# SCH_Bob_Endstops_2022-07-10.net
KiCad netlist of a schematic drawn in EasyEDA
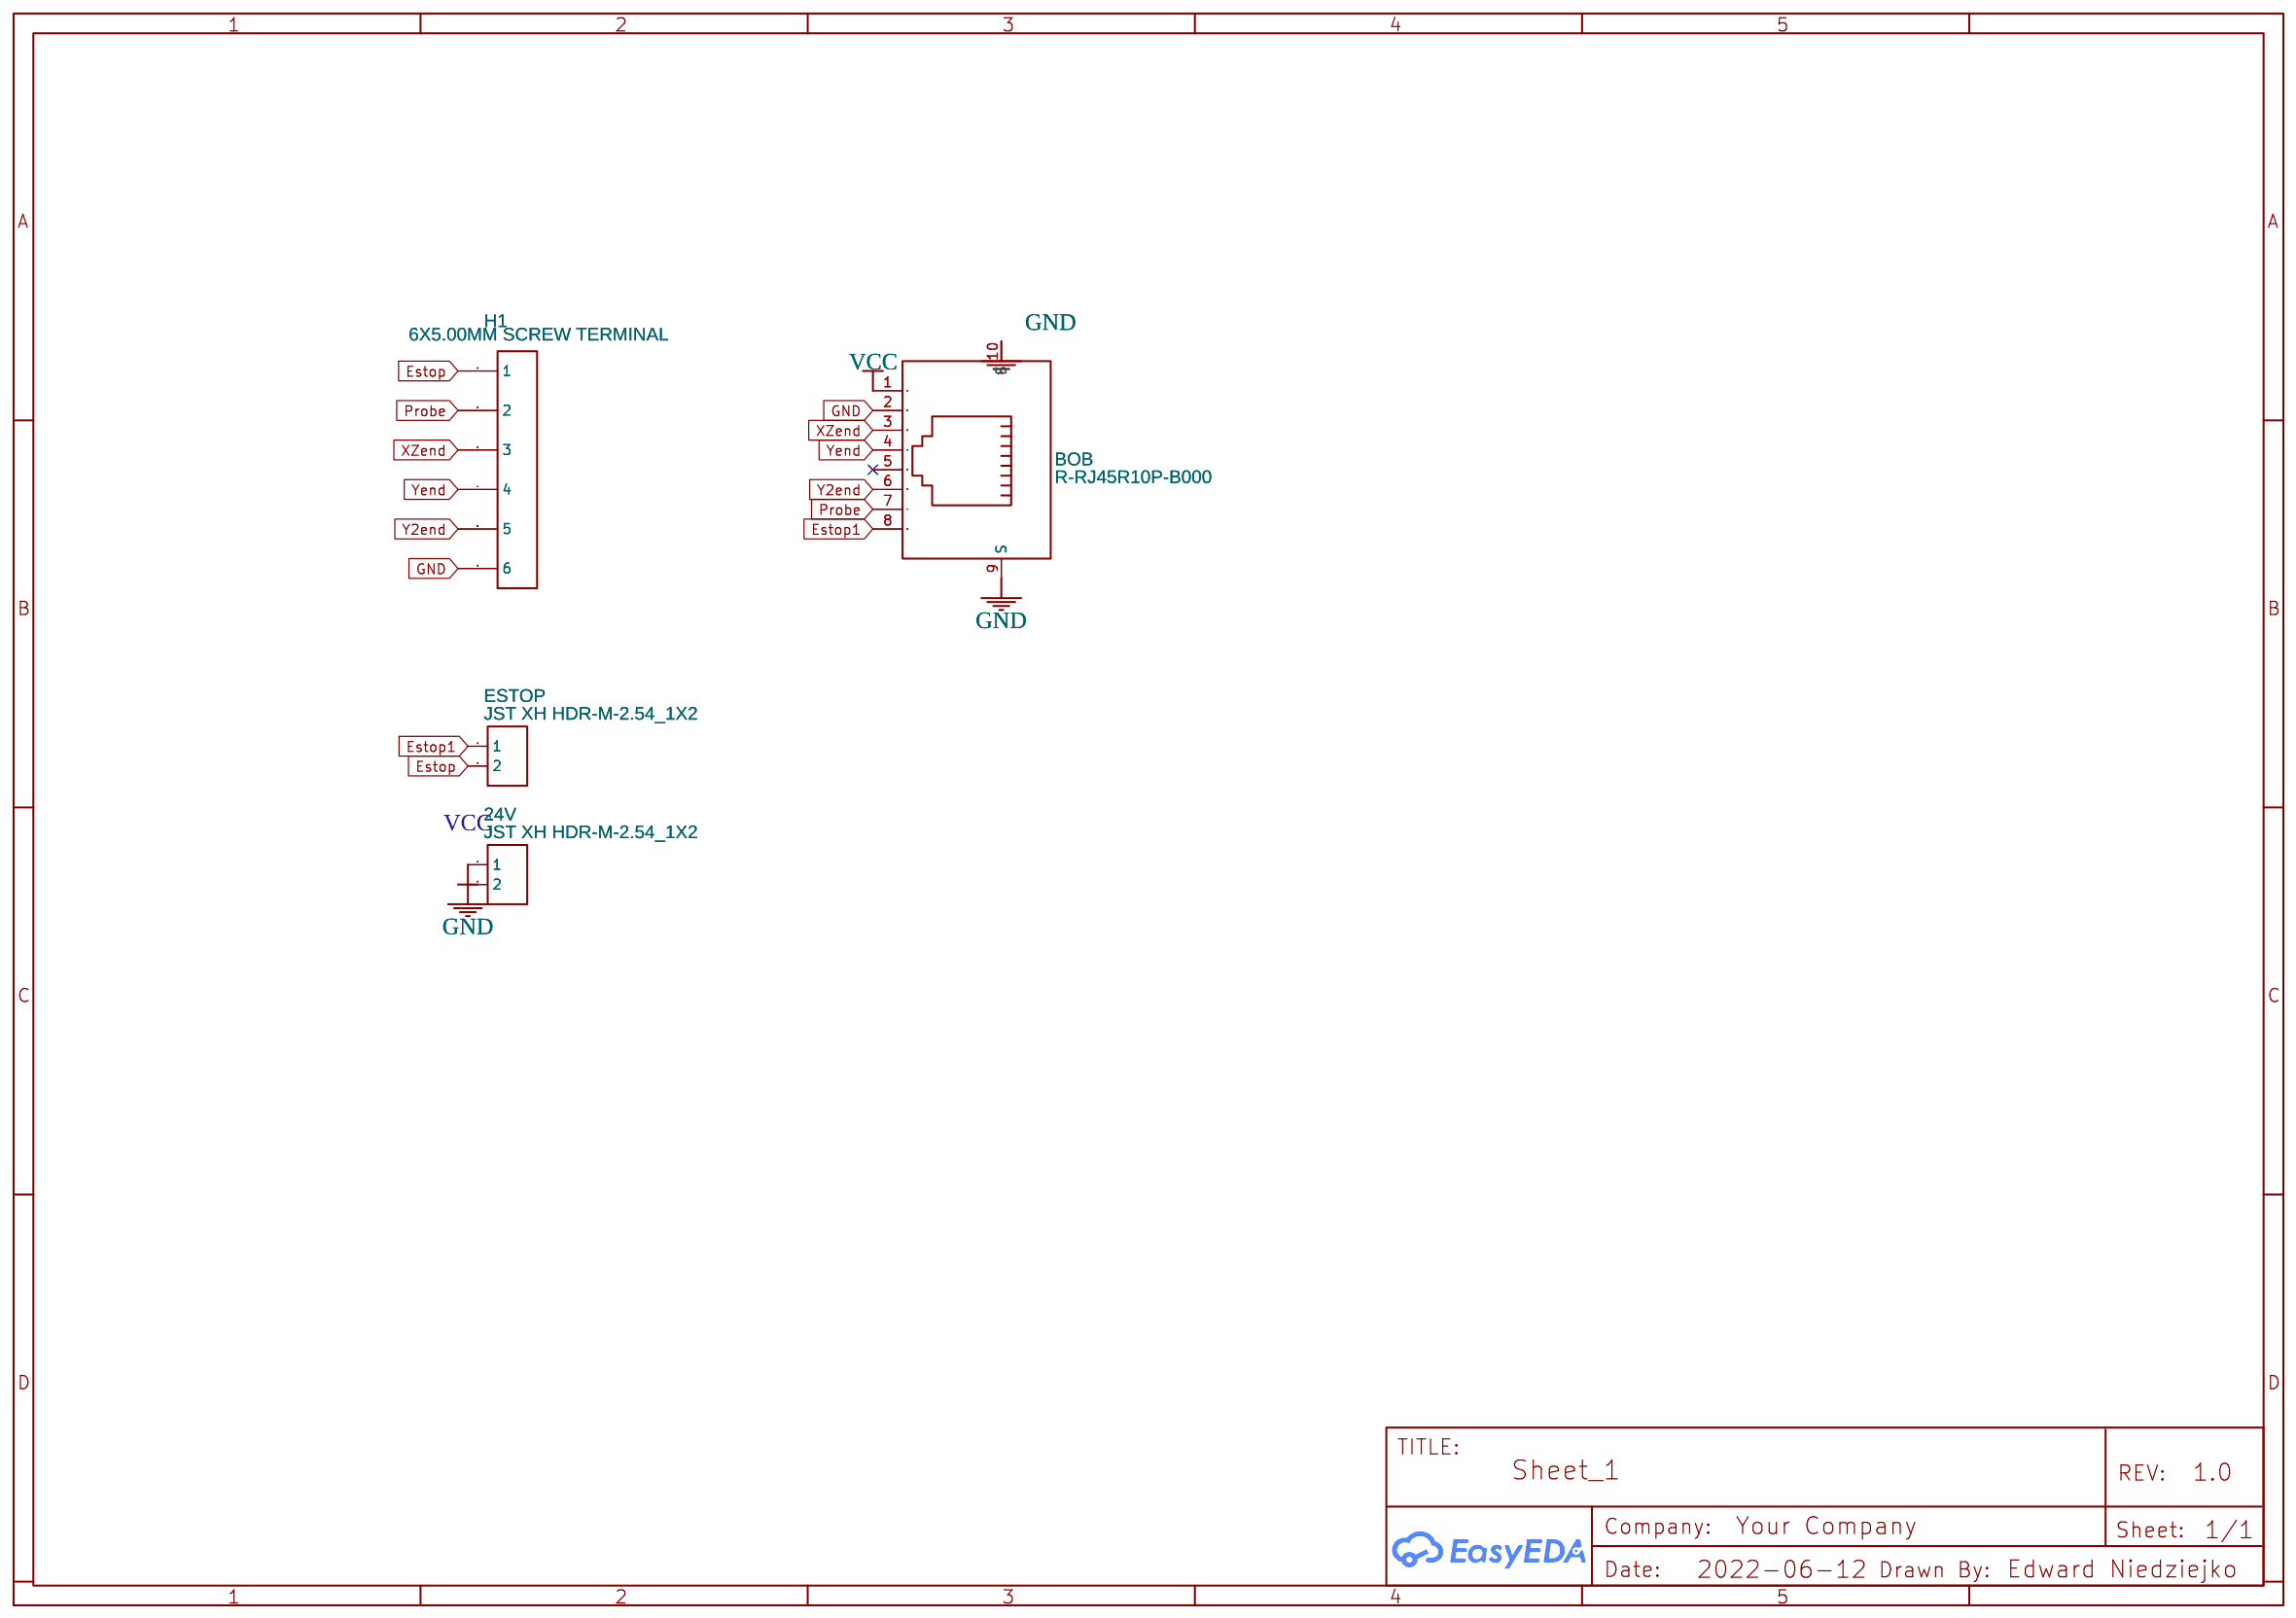
[diagram p0: schematic sheet]

(export (version "E")
  (design (tool "Eeschema 10.0.6"))
  (components
    (comp (ref "24V")
      (value "JST XH HDR-M-2.54_1X2")
      (fields (field (name "BOM_Supplier Part") "C49661"))
      (libsource (lib "") (part "JST XH HDR-M-2.54_1X2_1"))
    )
    (comp (ref "BOB")
      (value "R-RJ45R10P-B000")
      (fields (field (name "BOM_Supplier Part") "C386758"))
      (libsource (lib "") (part "R-RJ45R10P-B000"))
    )
    (comp (ref "ESTOP")
      (value "JST XH HDR-M-2.54_1X2")
      (fields (field (name "BOM_Supplier Part") "C49661"))
      (libsource (lib "") (part "JST XH HDR-M-2.54_1X2"))
    )
    (comp (ref "H1") (value "6X5.00MM SCREW TERMINAL") (libsource (lib "") (part "6X5.00MM SCREW TERMINAL")))
  )
  (nets
    (net (code "1") (name "Estop") (class "Default")
      (node (ref "ESTOP") (pin "2") (pinfunction "2_2") (pintype "input"))
      (node (ref "H1") (pin "1") (pinfunction "1_1") (pintype "unspecified"))
    )
    (net (code "2") (name "Estop1") (class "Default")
      (node (ref "BOB") (pin "8") (pinfunction "8_8") (pintype "unspecified"))
      (node (ref "ESTOP") (pin "1") (pinfunction "1_1") (pintype "input"))
    )
    (net (code "3") (name "GND") (class "Default")
      (node (ref "24V") (pin "2") (pinfunction "2_2") (pintype "input"))
      (node (ref "BOB") (pin "10") (pinfunction "S_10") (pintype "unspecified"))
      (node (ref "BOB") (pin "2") (pinfunction "2_2") (pintype "unspecified"))
      (node (ref "BOB") (pin "9") (pinfunction "S_9") (pintype "unspecified"))
      (node (ref "H1") (pin "6") (pinfunction "6_6") (pintype "unspecified"))
    )
    (net (code "4") (name "Probe") (class "Default")
      (node (ref "BOB") (pin "7") (pinfunction "7_7") (pintype "unspecified"))
      (node (ref "H1") (pin "2") (pinfunction "2_2") (pintype "unspecified"))
    )
    (net (code "5") (name "VCC") (class "Default")
      (node (ref "24V") (pin "1") (pinfunction "1_1") (pintype "input"))
      (node (ref "BOB") (pin "1") (pinfunction "1_1") (pintype "unspecified"))
    )
    (net (code "6") (name "XZend") (class "Default")
      (node (ref "BOB") (pin "3") (pinfunction "3_3") (pintype "unspecified"))
      (node (ref "H1") (pin "3") (pinfunction "3_3") (pintype "unspecified"))
    )
    (net (code "7") (name "Y2end") (class "Default")
      (node (ref "BOB") (pin "6") (pinfunction "6_6") (pintype "unspecified"))
      (node (ref "H1") (pin "5") (pinfunction "5_5") (pintype "unspecified"))
    )
    (net (code "8") (name "Yend") (class "Default")
      (node (ref "BOB") (pin "4") (pinfunction "4_4") (pintype "unspecified"))
      (node (ref "H1") (pin "4") (pinfunction "4_4") (pintype "unspecified"))
    )
    (net (code "9") (name "unconnected-(BOB-Pad5)") (class "Default")
      (node (ref "BOB") (pin "5") (pinfunction "5_5") (pintype "unspecified+no_connect"))
    )
  )
)
